# TAJ1051T.net
KiCad netlist of a schematic drawn in Altium Designer
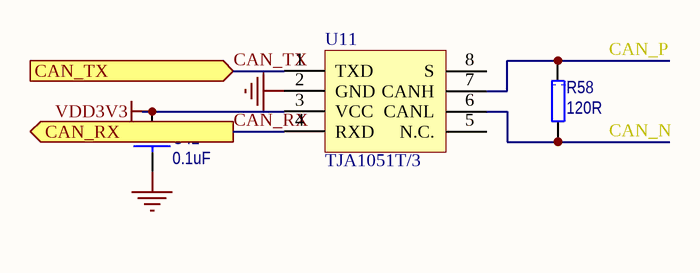
[diagram p0: TAJ1051T.SchDoc]

(export (version "E")
  (design (tool "Eeschema 10.0.6"))
  (components
    (comp (ref "C42")
      (value "0.1uF")
      (footprint "1608[0603]")
      (description "Capacitor")
      (fields (field (name "MANUFACTURER") "TDK"))
      (libsource (lib "*") (part "CAP"))
    )
    (comp (ref "R58")
      (value "120R")
      (footprint "1608[0603]R")
      (description "RES")
      (fields (field (name "MANUFACTURER") "vishay"))
      (libsource (lib "*") (part "RES"))
    )
    (comp (ref "U11")
      (value "TJA1051T/3")
      (footprint "SOIC-SN8_N")
      (description "IC")
      (libsource (lib "S3C2440V9") (part "TJA1051T/3"))
    )
  )
  (nets
    (net (code "1") (name "/CAN_N") (class "Default")
      (node (ref "R58") (pin "2") (pinfunction "2_2") (pintype "passive"))
      (node (ref "U11") (pin "6") (pinfunction "CANL_6") (pintype "passive"))
    )
    (net (code "2") (name "/CAN_P") (class "Default")
      (node (ref "R58") (pin "1") (pinfunction "1_1") (pintype "passive"))
      (node (ref "U11") (pin "7") (pinfunction "CANH_7") (pintype "passive"))
    )
    (net (code "3") (name "/CAN_RX") (class "Default")
      (node (ref "U11") (pin "4") (pinfunction "RXD_4") (pintype "passive"))
    )
    (net (code "4") (name "/CAN_TX") (class "Default")
      (node (ref "U11") (pin "1") (pinfunction "TXD_1") (pintype "passive"))
    )
    (net (code "5") (name "GND") (class "Default")
      (node (ref "C42") (pin "2") (pinfunction "2_2") (pintype "passive"))
      (node (ref "U11") (pin "2") (pinfunction "GND_2") (pintype "passive"))
    )
    (net (code "6") (name "VDD3V3") (class "Default")
      (node (ref "C42") (pin "1") (pinfunction "1_1") (pintype "passive"))
      (node (ref "U11") (pin "3") (pinfunction "VCC_3") (pintype "passive"))
    )
    (net (code "7") (name "unconnected-(U11-N.C.-Pad5)") (class "Default")
      (node (ref "U11") (pin "5") (pinfunction "N.C._5") (pintype "passive"))
    )
    (net (code "8") (name "unconnected-(U11-S-Pad8)") (class "Default")
      (node (ref "U11") (pin "8") (pinfunction "S_8") (pintype "passive"))
    )
  )
)
